# aprs_tracker_v5.net
KiCad netlist of a schematic drawn in EAGLE
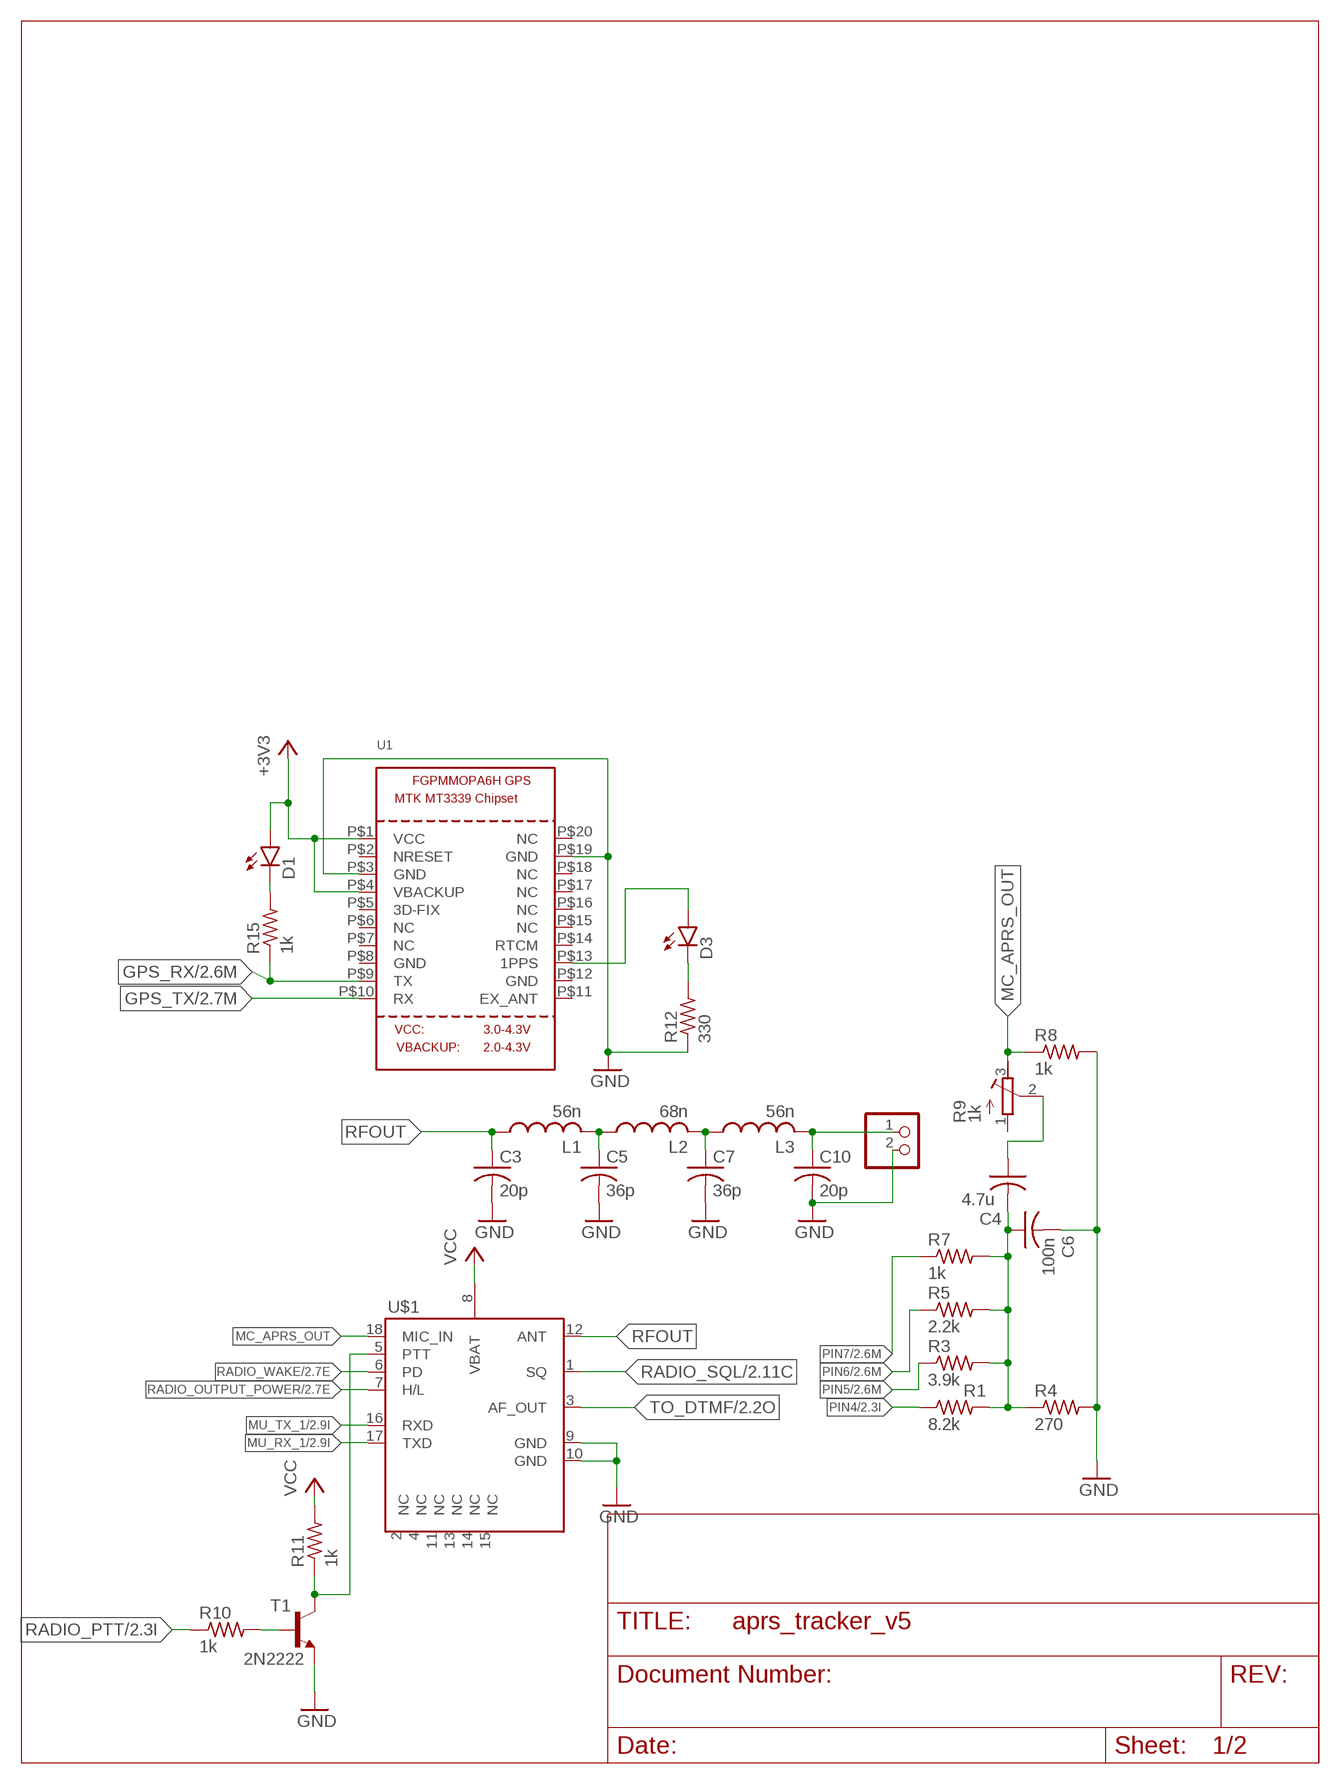
[diagram p0: schematic, sheet 1]
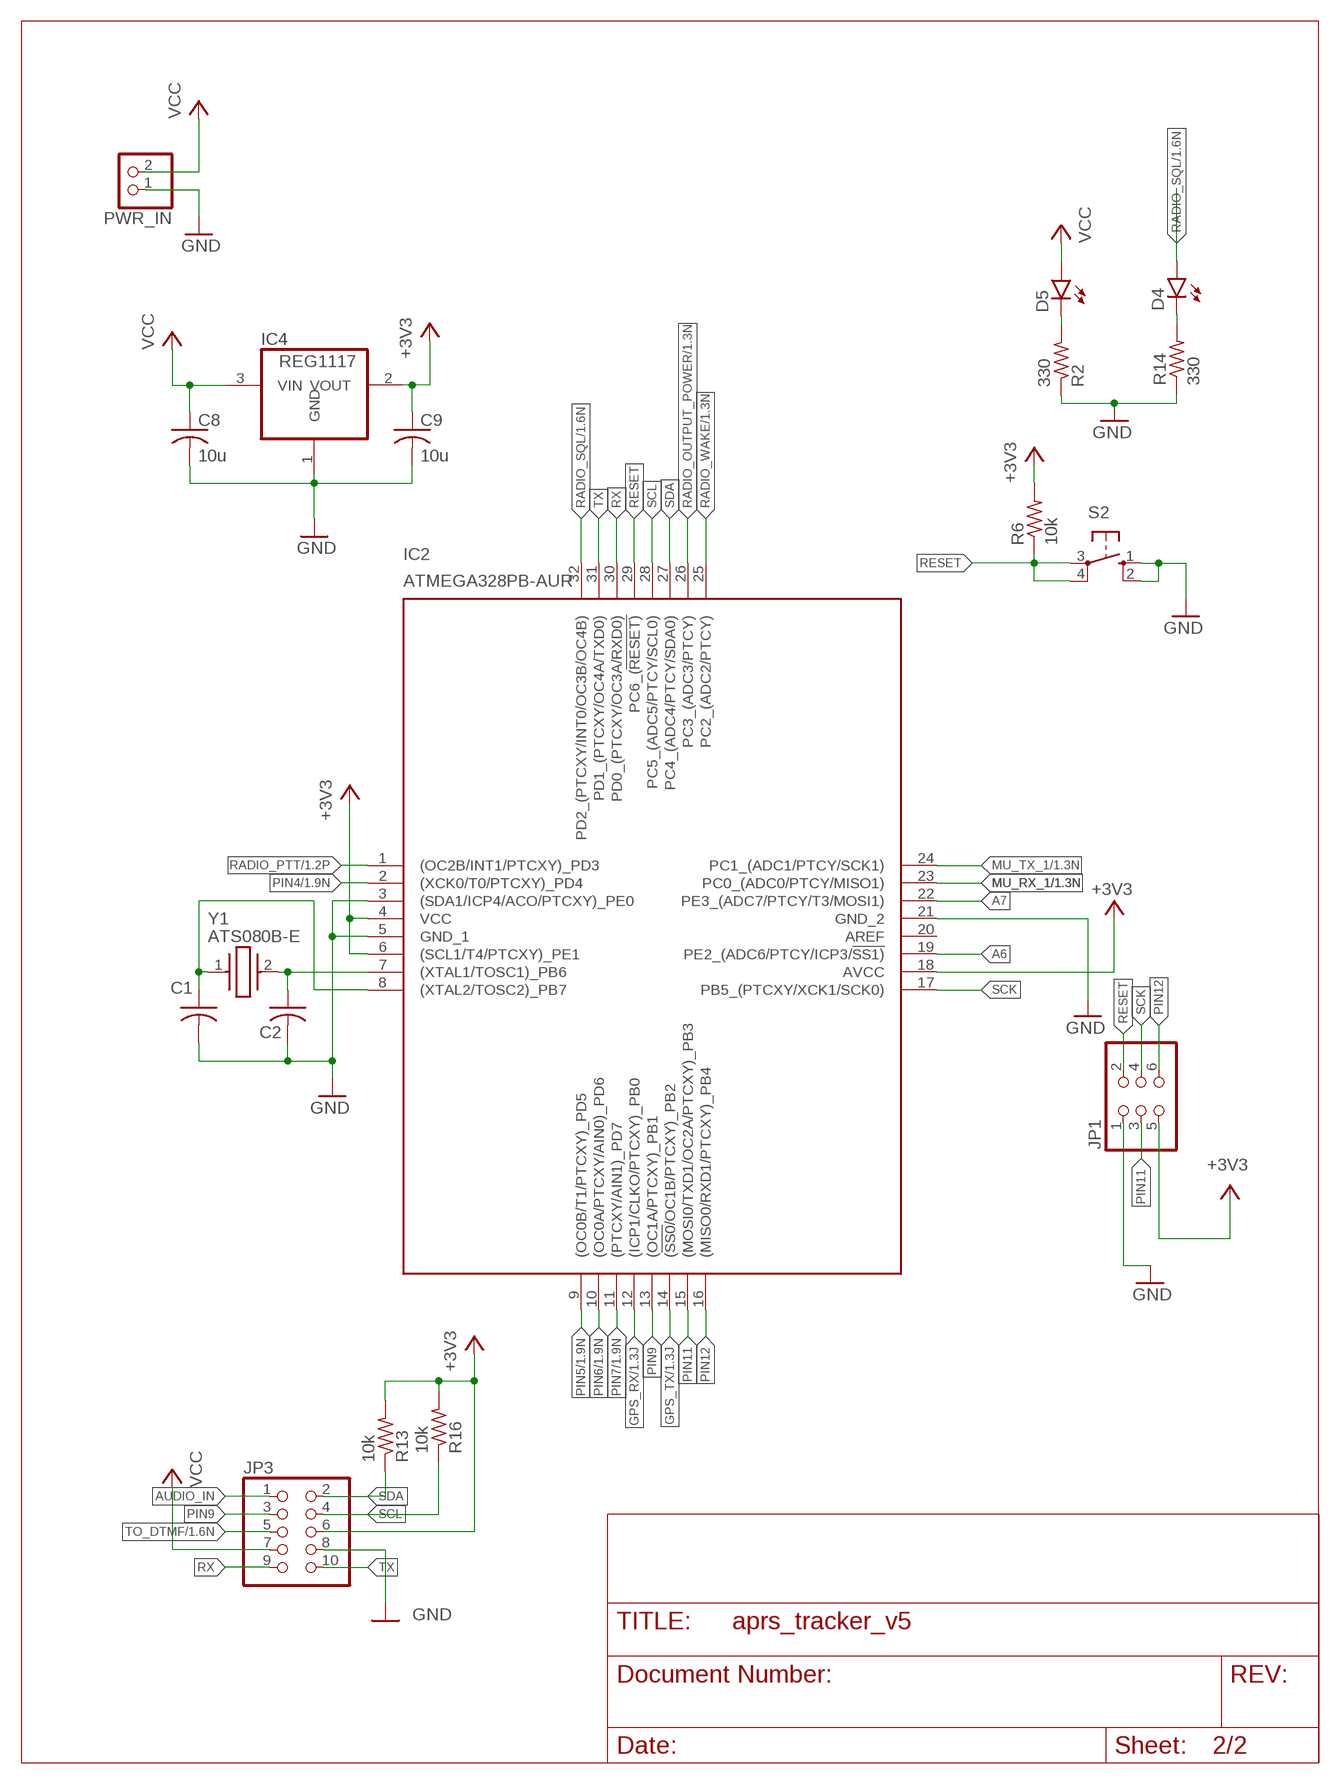
[diagram p1: schematic, sheet 2]

(export (version "E")
  (design (tool "Eeschema 10.0.6"))
  (components
    (comp (ref "C1")
      (value "C-USC0805")
      (footprint "eagle-import:C0805")
      (libsource (lib "eagle-import") (part "C-USC0805"))
    )
    (comp (ref "C2")
      (value "C-USC0805")
      (footprint "eagle-import:C0805")
      (libsource (lib "eagle-import") (part "C-USC0805"))
    )
    (comp (ref "C8")
      (value "10u")
      (footprint "eagle-import:C0805")
      (libsource (lib "eagle-import") (part "C-USC0805"))
    )
    (comp (ref "C9")
      (value "10u")
      (footprint "eagle-import:C0805")
      (libsource (lib "eagle-import") (part "C-USC0805"))
    )
    (comp (ref "D4")
      (value "LEDCHIP-LED0805")
      (footprint "eagle-import:CHIP-LED0805")
      (libsource (lib "eagle-import") (part "LEDCHIP-LED0805"))
    )
    (comp (ref "D5")
      (value "LEDCHIP-LED0805")
      (footprint "eagle-import:CHIP-LED0805")
      (libsource (lib "eagle-import") (part "LEDCHIP-LED0805"))
    )
    (comp (ref "IC2")
      (value "ATMEGA328PB-AUR")
      (footprint "eagle-import:QFP80P900X900X120-32N")
      (fields (field (name "MOUSER_PART_NUMBER") "556-ATMEGA328PB-AUR"))
      (libsource (lib "eagle-import") (part "ATMEGA328PB-AUR"))
    )
    (comp (ref "IC4")
      (value "REG1117")
      (footprint "eagle-import:SOT223")
      (libsource (lib "eagle-import") (part "REG1117"))
    )
    (comp (ref "JP1")
      (value "PINHD-2X3")
      (footprint "eagle-import:2X03")
      (libsource (lib "eagle-import") (part "PINHD-2X3"))
    )
    (comp (ref "JP3")
      (value "PINHD-2X5")
      (footprint "eagle-import:2X05")
      (libsource (lib "eagle-import") (part "PINHD-2X5"))
    )
    (comp (ref "PWR_IN")
      (value "PINHD-1X2")
      (footprint "eagle-import:1X02")
      (libsource (lib "eagle-import") (part "PINHD-1X2"))
    )
    (comp (ref "R2")
      (value "330")
      (footprint "eagle-import:R0805")
      (libsource (lib "eagle-import") (part "R-US_R0805"))
    )
    (comp (ref "R6")
      (value "10k")
      (footprint "eagle-import:R0805")
      (libsource (lib "eagle-import") (part "R-US_R0805"))
    )
    (comp (ref "R13")
      (value "10k")
      (footprint "eagle-import:R0805")
      (libsource (lib "eagle-import") (part "R-US_R0805"))
    )
    (comp (ref "R14")
      (value "330")
      (footprint "eagle-import:R0805")
      (libsource (lib "eagle-import") (part "R-US_R0805"))
    )
    (comp (ref "R16")
      (value "10k")
      (footprint "eagle-import:R0805")
      (libsource (lib "eagle-import") (part "R-US_R0805"))
    )
    (comp (ref "S2")
      (value "10-XX")
      (footprint "eagle-import:B3F-10XX")
      (fields (field (name "MPN") "B3F-1000"))
      (libsource (lib "eagle-import") (part "10-XX"))
    )
    (comp (ref "Y1")
      (value "ATS080B-E")
      (footprint "eagle-import:ATS080BE")
      (fields (field (name "MOUSER_PART_NUMBER") "774-ATS080B-E"))
      (libsource (lib "eagle-import") (part "ATS080B-E"))
    )
    (comp (ref "C3")
      (value "20p")
      (footprint "eagle-import:C0805K")
      (libsource (lib "eagle-import") (part "C-USC0805K"))
    )
    (comp (ref "C4")
      (value "4.7u")
      (footprint "eagle-import:C0805")
      (libsource (lib "eagle-import") (part "C-USC0805"))
    )
    (comp (ref "C5")
      (value "36p")
      (footprint "eagle-import:C0805K")
      (libsource (lib "eagle-import") (part "C-USC0805K"))
    )
    (comp (ref "C6")
      (value "100n")
      (footprint "eagle-import:C0805")
      (libsource (lib "eagle-import") (part "C-USC0805"))
    )
    (comp (ref "C7")
      (value "36p")
      (footprint "eagle-import:C0805K")
      (libsource (lib "eagle-import") (part "C-USC0805K"))
    )
    (comp (ref "C10")
      (value "20p")
      (footprint "eagle-import:C0805K")
      (libsource (lib "eagle-import") (part "C-USC0805K"))
    )
    (comp (ref "D1")
      (value "LEDCHIP-LED0805")
      (footprint "eagle-import:CHIP-LED0805")
      (libsource (lib "eagle-import") (part "LEDCHIP-LED0805"))
    )
    (comp (ref "D3")
      (value "LEDCHIP-LED0805")
      (footprint "eagle-import:CHIP-LED0805")
      (libsource (lib "eagle-import") (part "LEDCHIP-LED0805"))
    )
    (comp (ref "L1")
      (value "56n")
      (footprint "eagle-import:L3216C")
      (libsource (lib "eagle-import") (part "L-USL3216C"))
    )
    (comp (ref "L2")
      (value "68n")
      (footprint "eagle-import:L3216C")
      (libsource (lib "eagle-import") (part "L-USL3216C"))
    )
    (comp (ref "L3")
      (value "56n")
      (footprint "eagle-import:L3216C")
      (libsource (lib "eagle-import") (part "L-USL3216C"))
    )
    (comp (ref "R1")
      (value "8.2k")
      (footprint "eagle-import:R0805")
      (libsource (lib "eagle-import") (part "R-US_R0805"))
    )
    (comp (ref "R3")
      (value "3.9k")
      (footprint "eagle-import:R0805")
      (libsource (lib "eagle-import") (part "R-US_R0805"))
    )
    (comp (ref "R4")
      (value "270")
      (footprint "eagle-import:R0805")
      (libsource (lib "eagle-import") (part "R-US_R0805"))
    )
    (comp (ref "R5")
      (value "2.2k")
      (footprint "eagle-import:R0805")
      (libsource (lib "eagle-import") (part "R-US_R0805"))
    )
    (comp (ref "R7")
      (value "1k")
      (footprint "eagle-import:R0805")
      (libsource (lib "eagle-import") (part "R-US_R0805"))
    )
    (comp (ref "R8")
      (value "1k")
      (footprint "eagle-import:R0805")
      (libsource (lib "eagle-import") (part "R-US_R0805"))
    )
    (comp (ref "R9")
      (value "1k")
      (footprint "eagle-import:RTRIM3339P")
      (libsource (lib "eagle-import") (part "R-TRIMM3339P"))
    )
    (comp (ref "R10")
      (value "1k")
      (footprint "eagle-import:R0805")
      (libsource (lib "eagle-import") (part "R-US_R0805"))
    )
    (comp (ref "R11")
      (value "1k")
      (footprint "eagle-import:R0805")
      (libsource (lib "eagle-import") (part "R-US_R0805"))
    )
    (comp (ref "R12")
      (value "330")
      (footprint "eagle-import:R0805")
      (libsource (lib "eagle-import") (part "R-US_R0805"))
    )
    (comp (ref "R15")
      (value "1k")
      (footprint "eagle-import:R0805")
      (libsource (lib "eagle-import") (part "R-US_R0805"))
    )
    (comp (ref "T1")
      (value "2N2222")
      (footprint "eagle-import:TO92-EBC-OVAL")
      (libsource (lib "eagle-import") (part "2N2222"))
    )
    (comp (ref "U$1")
      (value "DRA818A")
      (footprint "eagle-import:DRA818A")
      (libsource (lib "eagle-import") (part "DRA818A"))
    )
    (comp (ref "U1")
      (value "GPS_FGPMMOPA6H")
      (footprint "eagle-import:FGPMMOPA6H")
      (libsource (lib "eagle-import") (part "GPS_FGPMMOPA6H"))
    )
    (comp (ref "X1")
      (value "PINHD-1X2")
      (footprint "eagle-import:1X02")
      (libsource (lib "eagle-import") (part "PINHD-1X2"))
    )
  )
  (nets
    (net (code "1") (name "+3V3") (class "Default")
      (node (ref "C9") (pin "1") (pinfunction "1_1") (pintype "passive"))
      (node (ref "D1") (pin "A") (pinfunction "A_A") (pintype "passive"))
      (node (ref "IC2") (pin "18") (pinfunction "AVCC_18") (pintype "bidirectional"))
      (node (ref "IC2") (pin "4") (pinfunction "VCC_4") (pintype "bidirectional"))
      (node (ref "IC2") (pin "6") (pinfunction "(SCL1/T4/PTCXY)_PE1_6") (pintype "bidirectional"))
      (node (ref "IC4") (pin "2") (pinfunction "VOUT_2") (pintype "output"))
      (node (ref "JP1") (pin "5") (pinfunction "5_5") (pintype "passive"))
      (node (ref "JP3") (pin "6") (pinfunction "6_6") (pintype "passive"))
      (node (ref "R13") (pin "2") (pinfunction "2_2") (pintype "passive"))
      (node (ref "R16") (pin "2") (pinfunction "2_2") (pintype "passive"))
      (node (ref "R6") (pin "2") (pinfunction "2_2") (pintype "passive"))
      (node (ref "U1") (pin "P$1") (pinfunction "VCC_P$1") (pintype "bidirectional"))
      (node (ref "U1") (pin "P$4") (pinfunction "VBACKUP_P$4") (pintype "bidirectional"))
    )
    (net (code "2") (name "A6") (class "Default")
      (node (ref "IC2") (pin "19") (pinfunction "PE2_(ADC6/PTCY/ICP3/~{SS1})_19") (pintype "bidirectional"))
    )
    (net (code "3") (name "A7") (class "Default")
      (node (ref "IC2") (pin "22") (pinfunction "PE3_(ADC7/PTCY/T3/MOSI1)_22") (pintype "bidirectional"))
    )
    (net (code "4") (name "AUDIO_IN") (class "Default")
      (node (ref "JP3") (pin "1") (pinfunction "1_1") (pintype "passive"))
    )
    (net (code "5") (name "GND") (class "Default")
      (node (ref "C1") (pin "2") (pinfunction "2_2") (pintype "passive"))
      (node (ref "C10") (pin "2") (pinfunction "2_2") (pintype "passive"))
      (node (ref "C2") (pin "2") (pinfunction "2_2") (pintype "passive"))
      (node (ref "C3") (pin "2") (pinfunction "2_2") (pintype "passive"))
      (node (ref "C5") (pin "2") (pinfunction "2_2") (pintype "passive"))
      (node (ref "C6") (pin "2") (pinfunction "2_2") (pintype "passive"))
      (node (ref "C7") (pin "2") (pinfunction "2_2") (pintype "passive"))
      (node (ref "C8") (pin "2") (pinfunction "2_2") (pintype "passive"))
      (node (ref "C9") (pin "2") (pinfunction "2_2") (pintype "passive"))
      (node (ref "IC2") (pin "21") (pinfunction "GND_2_21") (pintype "bidirectional"))
      (node (ref "IC2") (pin "3") (pinfunction "(SDA1/ICP4/ACO/PTCXY)_PE0_3") (pintype "bidirectional"))
      (node (ref "IC2") (pin "5") (pinfunction "GND_1_5") (pintype "bidirectional"))
      (node (ref "IC4") (pin "1") (pinfunction "GND_1") (pintype "power_in"))
      (node (ref "JP1") (pin "1") (pinfunction "1_1") (pintype "passive"))
      (node (ref "JP3") (pin "8") (pinfunction "8_8") (pintype "passive"))
      (node (ref "PWR_IN") (pin "1") (pinfunction "1_1") (pintype "passive"))
      (node (ref "R12") (pin "1") (pinfunction "1_1") (pintype "passive"))
      (node (ref "R14") (pin "1") (pinfunction "1_1") (pintype "passive"))
      (node (ref "R2") (pin "1") (pinfunction "1_1") (pintype "passive"))
      (node (ref "R4") (pin "2") (pinfunction "2_2") (pintype "passive"))
      (node (ref "R8") (pin "2") (pinfunction "2_2") (pintype "passive"))
      (node (ref "S2") (pin "1") (pinfunction "S_1") (pintype "passive"))
      (node (ref "S2") (pin "2") (pinfunction "S1_2") (pintype "passive"))
      (node (ref "T1") (pin "E") (pinfunction "E_E") (pintype "passive"))
      (node (ref "U$1") (pin "10") (pinfunction "GND_10") (pintype "bidirectional"))
      (node (ref "U$1") (pin "9") (pinfunction "GND_9") (pintype "bidirectional"))
      (node (ref "U1") (pin "P$19") (pinfunction "GND_P$19") (pintype "bidirectional"))
      (node (ref "U1") (pin "P$3") (pinfunction "GND_P$3") (pintype "bidirectional"))
      (node (ref "X1") (pin "2") (pinfunction "2_2") (pintype "passive"))
    )
    (net (code "6") (name "GPS_RX") (class "Default")
      (node (ref "IC2") (pin "12") (pinfunction "(ICP1/CLKO/PTCXY)_PB0_12") (pintype "bidirectional"))
      (node (ref "R15") (pin "1") (pinfunction "1_1") (pintype "passive"))
      (node (ref "U1") (pin "P$9") (pinfunction "TX_P$9") (pintype "bidirectional"))
    )
    (net (code "7") (name "GPS_TX") (class "Default")
      (node (ref "IC2") (pin "14") (pinfunction "(~{SS0}/OC1B/PTCXY)_PB2_14") (pintype "bidirectional"))
      (node (ref "U1") (pin "P$10") (pinfunction "RX_P$10") (pintype "bidirectional"))
    )
    (net (code "8") (name "MC_APRS_OUT") (class "Default")
      (node (ref "R8") (pin "1") (pinfunction "1_1") (pintype "passive"))
      (node (ref "R9") (pin "3") (pinfunction "E_3") (pintype "passive"))
      (node (ref "U$1") (pin "18") (pinfunction "MIC_IN_18") (pintype "bidirectional"))
    )
    (net (code "9") (name "MU_RX_1") (class "Default")
      (node (ref "IC2") (pin "23") (pinfunction "PC0_(ADC0/PTCY/MISO1)_23") (pintype "bidirectional"))
      (node (ref "U$1") (pin "17") (pinfunction "TXD_17") (pintype "bidirectional"))
    )
    (net (code "10") (name "MU_TX_1") (class "Default")
      (node (ref "IC2") (pin "24") (pinfunction "PC1_(ADC1/PTCY/SCK1)_24") (pintype "bidirectional"))
      (node (ref "U$1") (pin "16") (pinfunction "RXD_16") (pintype "bidirectional"))
    )
    (net (code "11") (name "Net-(C4-Pad2)") (class "Default")
      (node (ref "C4") (pin "2") (pinfunction "2_2") (pintype "passive"))
      (node (ref "C6") (pin "1") (pinfunction "1_1") (pintype "passive"))
      (node (ref "R1") (pin "2") (pinfunction "2_2") (pintype "passive"))
      (node (ref "R3") (pin "2") (pinfunction "2_2") (pintype "passive"))
      (node (ref "R4") (pin "1") (pinfunction "1_1") (pintype "passive"))
      (node (ref "R5") (pin "2") (pinfunction "2_2") (pintype "passive"))
      (node (ref "R7") (pin "2") (pinfunction "2_2") (pintype "passive"))
    )
    (net (code "12") (name "Net-(C5-Pad1)") (class "Default")
      (node (ref "C5") (pin "1") (pinfunction "1_1") (pintype "passive"))
      (node (ref "L1") (pin "2") (pinfunction "2_2") (pintype "passive"))
      (node (ref "L2") (pin "1") (pinfunction "1_1") (pintype "passive"))
    )
    (net (code "13") (name "Net-(C7-Pad1)") (class "Default")
      (node (ref "C7") (pin "1") (pinfunction "1_1") (pintype "passive"))
      (node (ref "L2") (pin "2") (pinfunction "2_2") (pintype "passive"))
      (node (ref "L3") (pin "1") (pinfunction "1_1") (pintype "passive"))
    )
    (net (code "14") (name "Net-(C10-Pad1)") (class "Default")
      (node (ref "C10") (pin "1") (pinfunction "1_1") (pintype "passive"))
      (node (ref "L3") (pin "2") (pinfunction "2_2") (pintype "passive"))
      (node (ref "X1") (pin "1") (pinfunction "1_1") (pintype "passive"))
    )
    (net (code "15") (name "Net-(D1-PadC)") (class "Default")
      (node (ref "D1") (pin "C") (pinfunction "C_C") (pintype "passive"))
      (node (ref "R15") (pin "2") (pinfunction "2_2") (pintype "passive"))
    )
    (net (code "16") (name "Net-(D3-PadC)") (class "Default")
      (node (ref "D3") (pin "C") (pinfunction "C_C") (pintype "passive"))
      (node (ref "R12") (pin "2") (pinfunction "2_2") (pintype "passive"))
    )
    (net (code "17") (name "Net-(D4-PadC)") (class "Default")
      (node (ref "D4") (pin "C") (pinfunction "C_C") (pintype "passive"))
      (node (ref "R14") (pin "2") (pinfunction "2_2") (pintype "passive"))
    )
    (net (code "18") (name "Net-(D5-PadC)") (class "Default")
      (node (ref "D5") (pin "C") (pinfunction "C_C") (pintype "passive"))
      (node (ref "R2") (pin "2") (pinfunction "2_2") (pintype "passive"))
    )
    (net (code "19") (name "Net-(IC2-(XTAL1{slash}TOSC1)_PB6)") (class "Default")
      (node (ref "C2") (pin "1") (pinfunction "1_1") (pintype "passive"))
      (node (ref "IC2") (pin "7") (pinfunction "(XTAL1/TOSC1)_PB6_7") (pintype "bidirectional"))
      (node (ref "Y1") (pin "2") (pinfunction "2_2") (pintype "bidirectional"))
    )
    (net (code "20") (name "Net-(IC2-(XTAL2{slash}TOSC2)_PB7)") (class "Default")
      (node (ref "C1") (pin "1") (pinfunction "1_1") (pintype "passive"))
      (node (ref "IC2") (pin "8") (pinfunction "(XTAL2/TOSC2)_PB7_8") (pintype "bidirectional"))
      (node (ref "Y1") (pin "1") (pinfunction "1_1") (pintype "bidirectional"))
    )
    (net (code "21") (name "Net-(R9-S)") (class "Default")
      (node (ref "C4") (pin "1") (pinfunction "1_1") (pintype "passive"))
      (node (ref "R9") (pin "2") (pinfunction "S_2") (pintype "passive"))
    )
    (net (code "22") (name "Net-(R10-Pad2)") (class "Default")
      (node (ref "R10") (pin "2") (pinfunction "2_2") (pintype "passive"))
      (node (ref "T1") (pin "B") (pinfunction "B_B") (pintype "passive"))
    )
    (net (code "23") (name "Net-(U$1-PTT)") (class "Default")
      (node (ref "R11") (pin "1") (pinfunction "1_1") (pintype "passive"))
      (node (ref "T1") (pin "C") (pinfunction "C_C") (pintype "passive"))
      (node (ref "U$1") (pin "5") (pinfunction "PTT_5") (pintype "bidirectional"))
    )
    (net (code "24") (name "Net-(U1-1PPS)") (class "Default")
      (node (ref "D3") (pin "A") (pinfunction "A_A") (pintype "passive"))
      (node (ref "U1") (pin "P$13") (pinfunction "1PPS_P$13") (pintype "bidirectional"))
    )
    (net (code "25") (name "PIN4") (class "Default")
      (node (ref "IC2") (pin "2") (pinfunction "(XCK0/T0/PTCXY)_PD4_2") (pintype "bidirectional"))
      (node (ref "R1") (pin "1") (pinfunction "1_1") (pintype "passive"))
    )
    (net (code "26") (name "PIN5") (class "Default")
      (node (ref "IC2") (pin "9") (pinfunction "(OC0B/T1/PTCXY)_PD5_9") (pintype "bidirectional"))
      (node (ref "R3") (pin "1") (pinfunction "1_1") (pintype "passive"))
    )
    (net (code "27") (name "PIN6") (class "Default")
      (node (ref "IC2") (pin "10") (pinfunction "(OC0A/PTCXY/AIN0)_PD6_10") (pintype "bidirectional"))
      (node (ref "R5") (pin "1") (pinfunction "1_1") (pintype "passive"))
    )
    (net (code "28") (name "PIN7") (class "Default")
      (node (ref "IC2") (pin "11") (pinfunction "(PTCXY/AIN1)_PD7_11") (pintype "bidirectional"))
      (node (ref "R7") (pin "1") (pinfunction "1_1") (pintype "passive"))
    )
    (net (code "29") (name "PIN9") (class "Default")
      (node (ref "IC2") (pin "13") (pinfunction "(OC1A/PTCXY)_PB1_13") (pintype "bidirectional"))
      (node (ref "JP3") (pin "3") (pinfunction "3_3") (pintype "passive"))
    )
    (net (code "30") (name "PIN11") (class "Default")
      (node (ref "IC2") (pin "15") (pinfunction "(MOSI0/TXD1/OC2A/PTCXY)_PB3_15") (pintype "bidirectional"))
      (node (ref "JP1") (pin "3") (pinfunction "3_3") (pintype "passive"))
    )
    (net (code "31") (name "PIN12") (class "Default")
      (node (ref "IC2") (pin "16") (pinfunction "(MISO0/RXD1/PTCXY)_PB4_16") (pintype "bidirectional"))
      (node (ref "JP1") (pin "6") (pinfunction "6_6") (pintype "passive"))
    )
    (net (code "32") (name "RADIO_OUTPUT_POWER") (class "Default")
      (node (ref "IC2") (pin "26") (pinfunction "PC3_(ADC3/PTCY)_26") (pintype "bidirectional"))
      (node (ref "U$1") (pin "7") (pinfunction "H/L_7") (pintype "bidirectional"))
    )
    (net (code "33") (name "RADIO_PTT") (class "Default")
      (node (ref "IC2") (pin "1") (pinfunction "(OC2B/INT1/PTCXY)_PD3_1") (pintype "bidirectional"))
      (node (ref "R10") (pin "1") (pinfunction "1_1") (pintype "passive"))
    )
    (net (code "34") (name "RADIO_SQL") (class "Default")
      (node (ref "D4") (pin "A") (pinfunction "A_A") (pintype "passive"))
      (node (ref "IC2") (pin "32") (pinfunction "PD2_(PTCXY/INT0/OC3B/OC4B)_32") (pintype "bidirectional"))
      (node (ref "U$1") (pin "1") (pinfunction "SQ_1") (pintype "bidirectional"))
    )
    (net (code "35") (name "RADIO_WAKE") (class "Default")
      (node (ref "IC2") (pin "25") (pinfunction "PC2_(ADC2/PTCY)_25") (pintype "bidirectional"))
      (node (ref "U$1") (pin "6") (pinfunction "PD_6") (pintype "bidirectional"))
    )
    (net (code "36") (name "RESET") (class "Default")
      (node (ref "IC2") (pin "29") (pinfunction "PC6_(~{RESET})_29") (pintype "bidirectional"))
      (node (ref "JP1") (pin "2") (pinfunction "2_2") (pintype "passive"))
      (node (ref "R6") (pin "1") (pinfunction "1_1") (pintype "passive"))
      (node (ref "S2") (pin "3") (pinfunction "P_3") (pintype "passive"))
      (node (ref "S2") (pin "4") (pinfunction "P1_4") (pintype "passive"))
    )
    (net (code "37") (name "RFOUT") (class "Default")
      (node (ref "C3") (pin "1") (pinfunction "1_1") (pintype "passive"))
      (node (ref "L1") (pin "1") (pinfunction "1_1") (pintype "passive"))
      (node (ref "U$1") (pin "12") (pinfunction "ANT_12") (pintype "bidirectional"))
    )
    (net (code "38") (name "RX") (class "Default")
      (node (ref "IC2") (pin "30") (pinfunction "PD0_(PTCXY/OC3A/RXD0)_30") (pintype "bidirectional"))
      (node (ref "JP3") (pin "9") (pinfunction "9_9") (pintype "passive"))
    )
    (net (code "39") (name "SCK") (class "Default")
      (node (ref "IC2") (pin "17") (pinfunction "PB5_(PTCXY/XCK1/SCK0)_17") (pintype "bidirectional"))
      (node (ref "JP1") (pin "4") (pinfunction "4_4") (pintype "passive"))
    )
    (net (code "40") (name "SCL") (class "Default")
      (node (ref "IC2") (pin "28") (pinfunction "PC5_(ADC5/PTCY/SCL0)_28") (pintype "bidirectional"))
      (node (ref "JP3") (pin "4") (pinfunction "4_4") (pintype "passive"))
      (node (ref "R16") (pin "1") (pinfunction "1_1") (pintype "passive"))
    )
    (net (code "41") (name "SDA") (class "Default")
      (node (ref "IC2") (pin "27") (pinfunction "PC4_(ADC4/PTCY/SDA0)_27") (pintype "bidirectional"))
      (node (ref "JP3") (pin "2") (pinfunction "2_2") (pintype "passive"))
      (node (ref "R13") (pin "1") (pinfunction "1_1") (pintype "passive"))
    )
    (net (code "42") (name "TO_DTMF") (class "Default")
      (node (ref "JP3") (pin "5") (pinfunction "5_5") (pintype "passive"))
      (node (ref "U$1") (pin "3") (pinfunction "AF_OUT_3") (pintype "bidirectional"))
    )
    (net (code "43") (name "TX") (class "Default")
      (node (ref "IC2") (pin "31") (pinfunction "PD1_(PTCXY/OC4A/TXD0)_31") (pintype "bidirectional"))
      (node (ref "JP3") (pin "10") (pinfunction "10_10") (pintype "passive"))
    )
    (net (code "44") (name "VCC") (class "Default")
      (node (ref "C8") (pin "1") (pinfunction "1_1") (pintype "passive"))
      (node (ref "D5") (pin "A") (pinfunction "A_A") (pintype "passive"))
      (node (ref "IC4") (pin "3") (pinfunction "VIN_3") (pintype "input"))
      (node (ref "JP3") (pin "7") (pinfunction "7_7") (pintype "passive"))
      (node (ref "PWR_IN") (pin "2") (pinfunction "2_2") (pintype "passive"))
      (node (ref "R11") (pin "2") (pinfunction "2_2") (pintype "passive"))
      (node (ref "U$1") (pin "8") (pinfunction "VBAT_8") (pintype "bidirectional"))
    )
    (net (code "45") (name "unconnected-(IC2-AREF-Pad20)") (class "Default")
      (node (ref "IC2") (pin "20") (pinfunction "AREF_20") (pintype "bidirectional"))
    )
    (net (code "46") (name "unconnected-(R9-A-Pad1)") (class "Default")
      (node (ref "R9") (pin "1") (pinfunction "A_1") (pintype "passive"))
    )
    (net (code "47") (name "unconnected-(U$1-NC-Pad2)") (class "Default")
      (node (ref "U$1") (pin "2") (pinfunction "NC_2") (pintype "bidirectional"))
    )
    (net (code "48") (name "unconnected-(U$1-NC-Pad4)") (class "Default")
      (node (ref "U$1") (pin "4") (pinfunction "NC_4") (pintype "bidirectional"))
    )
    (net (code "49") (name "unconnected-(U$1-NC-Pad11)") (class "Default")
      (node (ref "U$1") (pin "11") (pinfunction "NC_11") (pintype "bidirectional"))
    )
    (net (code "50") (name "unconnected-(U$1-NC-Pad13)") (class "Default")
      (node (ref "U$1") (pin "13") (pinfunction "NC_13") (pintype "bidirectional"))
    )
    (net (code "51") (name "unconnected-(U$1-NC-Pad14)") (class "Default")
      (node (ref "U$1") (pin "14") (pinfunction "NC_14") (pintype "bidirectional"))
    )
    (net (code "52") (name "unconnected-(U$1-NC-Pad15)") (class "Default")
      (node (ref "U$1") (pin "15") (pinfunction "NC_15") (pintype "bidirectional"))
    )
    (net (code "53") (name "unconnected-(U1-3D-FIX-PadP$5)") (class "Default")
      (node (ref "U1") (pin "P$5") (pinfunction "3D-FIX_P$5") (pintype "bidirectional"))
    )
    (net (code "54") (name "unconnected-(U1-EX_ANT-PadP$11)") (class "Default")
      (node (ref "U1") (pin "P$11") (pinfunction "EX_ANT_P$11") (pintype "bidirectional"))
    )
    (net (code "55") (name "unconnected-(U1-GND-PadP$8)") (class "Default")
      (node (ref "U1") (pin "P$8") (pinfunction "GND_P$8") (pintype "bidirectional"))
    )
    (net (code "56") (name "unconnected-(U1-GND-PadP$12)") (class "Default")
      (node (ref "U1") (pin "P$12") (pinfunction "GND_P$12") (pintype "bidirectional"))
    )
    (net (code "57") (name "unconnected-(U1-NC-PadP$6)") (class "Default")
      (node (ref "U1") (pin "P$6") (pinfunction "NC_P$6") (pintype "bidirectional"))
    )
    (net (code "58") (name "unconnected-(U1-NC-PadP$7)") (class "Default")
      (node (ref "U1") (pin "P$7") (pinfunction "NC_P$7") (pintype "bidirectional"))
    )
    (net (code "59") (name "unconnected-(U1-NC-PadP$15)") (class "Default")
      (node (ref "U1") (pin "P$15") (pinfunction "NC_P$15") (pintype "bidirectional"))
    )
    (net (code "60") (name "unconnected-(U1-NC-PadP$16)") (class "Default")
      (node (ref "U1") (pin "P$16") (pinfunction "NC_P$16") (pintype "bidirectional"))
    )
    (net (code "61") (name "unconnected-(U1-NC-PadP$17)") (class "Default")
      (node (ref "U1") (pin "P$17") (pinfunction "NC_P$17") (pintype "bidirectional"))
    )
    (net (code "62") (name "unconnected-(U1-NC-PadP$18)") (class "Default")
      (node (ref "U1") (pin "P$18") (pinfunction "NC_P$18") (pintype "bidirectional"))
    )
    (net (code "63") (name "unconnected-(U1-NC-PadP$20)") (class "Default")
      (node (ref "U1") (pin "P$20") (pinfunction "NC_P$20") (pintype "bidirectional"))
    )
    (net (code "64") (name "unconnected-(U1-NRESET-PadP$2)") (class "Default")
      (node (ref "U1") (pin "P$2") (pinfunction "NRESET_P$2") (pintype "bidirectional"))
    )
    (net (code "65") (name "unconnected-(U1-RTCM-PadP$14)") (class "Default")
      (node (ref "U1") (pin "P$14") (pinfunction "RTCM_P$14") (pintype "bidirectional"))
    )
  )
)
